# cpu_rev2.net
KiCad netlist of a schematic drawn in Altium Designer
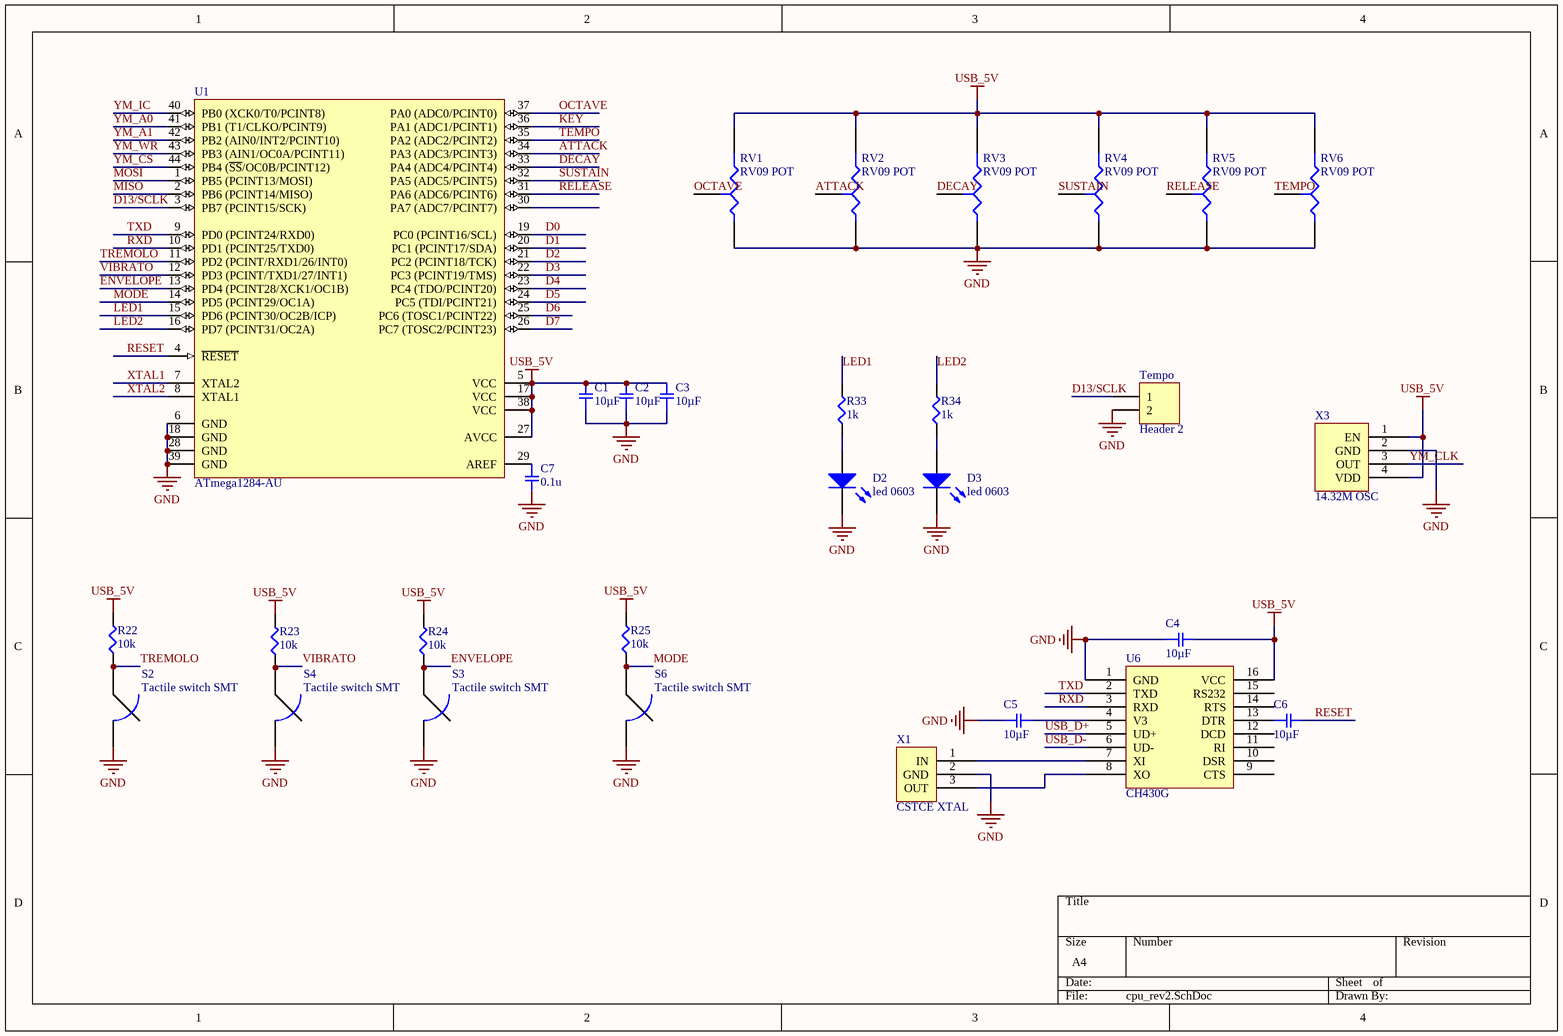
[diagram p0: cpu_rev2.SchDoc]

(export (version "E")
  (design (tool "Eeschema 10.0.6"))
  (components
    (comp (ref "C1")
      (value "10µF")
      (footprint "SMD-0805C")
      (description "CAP CER 10UF 6.3V X5R 0805")
      (fields
        (field (name "DIGI-KEY PART NUMBER") "490-3340-1-ND")
        (field (name "PART NUMBER") "GRM219R60J106KE19D")
      )
      (libsource (lib "capacitor_murata_0805") (part "GRM219R60J106KE19D"))
    )
    (comp (ref "C2")
      (value "10µF")
      (footprint "SMD-0805C")
      (description "CAP CER 10UF 6.3V X5R 0805")
      (fields
        (field (name "DIGI-KEY PART NUMBER") "490-3340-1-ND")
        (field (name "PART NUMBER") "GRM219R60J106KE19D")
      )
      (libsource (lib "capacitor_murata_0805") (part "GRM219R60J106KE19D"))
    )
    (comp (ref "C3")
      (value "10µF")
      (footprint "SMD-0805C")
      (description "CAP CER 10UF 6.3V X5R 0805")
      (fields
        (field (name "DIGI-KEY PART NUMBER") "490-3340-1-ND")
        (field (name "PART NUMBER") "GRM219R60J106KE19D")
      )
      (libsource (lib "capacitor_murata_0805") (part "GRM219R60J106KE19D"))
    )
    (comp (ref "C4")
      (value "10µF")
      (footprint "SMD-0805C")
      (description "CAP CER 10UF 6.3V X5R 0805")
      (fields
        (field (name "DIGI-KEY PART NUMBER") "490-3340-1-ND")
        (field (name "PART NUMBER") "GRM219R60J106KE19D")
      )
      (libsource (lib "capacitor_murata_0805") (part "GRM219R60J106KE19D"))
    )
    (comp (ref "C5")
      (value "10µF")
      (footprint "SMD-0805C")
      (description "CAP CER 10UF 6.3V X5R 0805")
      (fields
        (field (name "DIGI-KEY PART NUMBER") "490-3340-1-ND")
        (field (name "PART NUMBER") "GRM219R60J106KE19D")
      )
      (libsource (lib "capacitor_murata_0805") (part "GRM219R60J106KE19D"))
    )
    (comp (ref "C6")
      (value "10µF")
      (footprint "SMD-0805C")
      (description "CAP CER 10UF 6.3V X5R 0805")
      (fields
        (field (name "DIGI-KEY PART NUMBER") "490-3340-1-ND")
        (field (name "PART NUMBER") "GRM219R60J106KE19D")
      )
      (libsource (lib "capacitor_murata_0805") (part "GRM219R60J106KE19D"))
    )
    (comp (ref "C7")
      (value "0.1u")
      (footprint "SMD-0805C")
      (description "CAP CER 10000PF 25V X7R 0805")
      (fields
        (field (name "DIGI-KEY PART NUMBER") "490-12748-1-ND")
        (field (name "PART NUMBER") "GRM216R71E103KA01D")
      )
      (libsource (lib "capacitor_murata_0805") (part "GRM216R71E103KA01D"))
    )
    (comp (ref "D2")
      (value "led 0603")
      (footprint "led 0603")
      (libsource (lib "honglong_library") (part "led 0603"))
    )
    (comp (ref "D3")
      (value "led 0603")
      (footprint "led 0603")
      (libsource (lib "honglong_library") (part "led 0603"))
    )
    (comp (ref "R22")
      (value "10k")
      (footprint "SMD-0603-RES")
      (description "RES SMD 10K OHM 1% 1/10W 0603")
      (fields
        (field (name "PART NUMBER") "ERJ-3EKF1002V")
        (field (name "DIGI-KEY PART NUMBER") "P10.0KHCT-ND")
      )
      (libsource (lib "Panasonic_ERJ_0603") (part "ERJ-3EKF1002V"))
    )
    (comp (ref "R23")
      (value "10k")
      (footprint "SMD-0603-RES")
      (description "RES SMD 10K OHM 1% 1/10W 0603")
      (fields
        (field (name "PART NUMBER") "ERJ-3EKF1002V")
        (field (name "DIGI-KEY PART NUMBER") "P10.0KHCT-ND")
      )
      (libsource (lib "Panasonic_ERJ_0603") (part "ERJ-3EKF1002V"))
    )
    (comp (ref "R24")
      (value "10k")
      (footprint "SMD-0603-RES")
      (description "RES SMD 10K OHM 1% 1/10W 0603")
      (fields
        (field (name "PART NUMBER") "ERJ-3EKF1002V")
        (field (name "DIGI-KEY PART NUMBER") "P10.0KHCT-ND")
      )
      (libsource (lib "Panasonic_ERJ_0603") (part "ERJ-3EKF1002V"))
    )
    (comp (ref "R25")
      (value "10k")
      (footprint "SMD-0603-RES")
      (description "RES SMD 10K OHM 1% 1/10W 0603")
      (fields
        (field (name "PART NUMBER") "ERJ-3EKF1002V")
        (field (name "DIGI-KEY PART NUMBER") "P10.0KHCT-ND")
      )
      (libsource (lib "Panasonic_ERJ_0603") (part "ERJ-3EKF1002V"))
    )
    (comp (ref "R33")
      (value "1k")
      (footprint "SMD-0805-RES")
      (description "RES SMD 1K OHM 1% 1/2W 0805")
      (fields
        (field (name "PART NUMBER") "ERJ-P06F1001V")
        (field (name "DIGI-KEY PART NUMBER") "P16058CT-ND")
      )
      (libsource (lib "Panasonic_ERJ_0805") (part "ERJ-P06F1001V"))
    )
    (comp (ref "R34")
      (value "1k")
      (footprint "SMD-0805-RES")
      (description "RES SMD 1K OHM 1% 1/2W 0805")
      (fields
        (field (name "PART NUMBER") "ERJ-P06F1001V")
        (field (name "DIGI-KEY PART NUMBER") "P16058CT-ND")
      )
      (libsource (lib "Panasonic_ERJ_0805") (part "ERJ-P06F1001V"))
    )
    (comp (ref "RV1") (value "RV09 POT") (footprint "RV09") (libsource (lib "slide") (part "RV09 POT")))
    (comp (ref "RV2") (value "RV09 POT") (footprint "RV09") (libsource (lib "slide") (part "RV09 POT")))
    (comp (ref "RV3") (value "RV09 POT") (footprint "RV09") (libsource (lib "slide") (part "RV09 POT")))
    (comp (ref "RV4") (value "RV09 POT") (footprint "RV09") (libsource (lib "slide") (part "RV09 POT")))
    (comp (ref "RV5") (value "RV09 POT") (footprint "RV09") (libsource (lib "slide") (part "RV09 POT")))
    (comp (ref "RV6") (value "RV09 POT") (footprint "RV09") (libsource (lib "slide") (part "RV09 POT")))
    (comp (ref "S2")
      (value "Tactile switch SMT")
      (footprint "Tactile switch SMT")
      (libsource (lib "roundie") (part "Tactile switch SMT"))
    )
    (comp (ref "S3")
      (value "Tactile switch SMT")
      (footprint "Tactile switch SMT")
      (libsource (lib "roundie") (part "Tactile switch SMT"))
    )
    (comp (ref "S4")
      (value "Tactile switch SMT")
      (footprint "Tactile switch SMT")
      (libsource (lib "roundie") (part "Tactile switch SMT"))
    )
    (comp (ref "S6")
      (value "Tactile switch SMT")
      (footprint "Tactile switch SMT")
      (libsource (lib "roundie") (part "Tactile switch SMT"))
    )
    (comp (ref "Tempo")
      (value "Header 2")
      (footprint "HDR1X2")
      (description "Header, 2-Pin")
      (fields (field (name "PUBLISHER") "Altium Limited"))
      (libsource (lib "Miscellaneous Connectors") (part "Header 2"))
    )
    (comp (ref "U1")
      (value "ATmega1284-AU")
      (footprint "44A_N")
      (fields (field (name "PUBLISHER") "Altium Limited"))
      (libsource (lib "Atmel Microcontroller 8-Bit megaAVR") (part "ATmega1284-AU"))
    )
    (comp (ref "U6") (value "CH430G") (footprint "CH430G") (libsource (lib "slide") (part "CH430G")))
    (comp (ref "X1")
      (value "CSTCE XTAL")
      (footprint "CSTCE-CCM-R0")
      (description "CST XTAL")
      (libsource (lib "slide") (part "CSTCE XTAL"))
    )
    (comp (ref "X3") (value "14.32M OSC") (footprint "OSC") (libsource (lib "slide") (part "14.32M OSC")))
  )
  (nets
    (net (code "1") (name "/ATTACK") (class "Default")
      (node (ref "RV2") (pin "2") (pinfunction "TAP_2") (pintype "passive"))
      (node (ref "U1") (pin "34") (pinfunction "PA3_(ADC3/PCINT3)_34") (pintype "bidirectional"))
    )
    (net (code "2") (name "/D0") (class "Default")
      (node (ref "U1") (pin "19") (pinfunction "PC0_(PCINT16/SCL)_19") (pintype "bidirectional"))
    )
    (net (code "3") (name "/D1") (class "Default")
      (node (ref "U1") (pin "20") (pinfunction "PC1_(PCINT17/SDA)_20") (pintype "bidirectional"))
    )
    (net (code "4") (name "/D2") (class "Default")
      (node (ref "U1") (pin "21") (pinfunction "PC2_(PCINT18/TCK)_21") (pintype "bidirectional"))
    )
    (net (code "5") (name "/D3") (class "Default")
      (node (ref "U1") (pin "22") (pinfunction "PC3_(PCINT19/TMS)_22") (pintype "bidirectional"))
    )
    (net (code "6") (name "/D4") (class "Default")
      (node (ref "U1") (pin "23") (pinfunction "PC4_(TDO/PCINT20)_23") (pintype "bidirectional"))
    )
    (net (code "7") (name "/D5") (class "Default")
      (node (ref "U1") (pin "24") (pinfunction "PC5_(TDI/PCINT21)_24") (pintype "bidirectional"))
    )
    (net (code "8") (name "/D6") (class "Default")
      (node (ref "U1") (pin "25") (pinfunction "PC6_(TOSC1/PCINT22)_25") (pintype "bidirectional"))
    )
    (net (code "9") (name "/D7") (class "Default")
      (node (ref "U1") (pin "26") (pinfunction "PC7_(TOSC2/PCINT23)_26") (pintype "bidirectional"))
    )
    (net (code "10") (name "/D13{slash}SCLK") (class "Default")
      (node (ref "Tempo") (pin "1") (pinfunction "1_1") (pintype "passive"))
      (node (ref "U1") (pin "3") (pinfunction "PB7_(PCINT15/SCK)_3") (pintype "bidirectional"))
    )
    (net (code "11") (name "/DECAY") (class "Default")
      (node (ref "RV3") (pin "2") (pinfunction "TAP_2") (pintype "passive"))
      (node (ref "U1") (pin "33") (pinfunction "PA4_(ADC4/PCINT4)_33") (pintype "bidirectional"))
    )
    (net (code "12") (name "/ENVELOPE") (class "Default")
      (node (ref "R24") (pin "1") (pinfunction "1_1") (pintype "passive"))
      (node (ref "S3") (pin "1") (pinfunction "1_1") (pintype "passive"))
      (node (ref "U1") (pin "13") (pinfunction "PD4_(PCINT28/XCK1/OC1B)_13") (pintype "bidirectional"))
    )
    (net (code "13") (name "/KEY") (class "Default")
      (node (ref "U1") (pin "36") (pinfunction "PA1_(ADC1/PCINT1)_36") (pintype "bidirectional"))
    )
    (net (code "14") (name "/LED1") (class "Default")
      (node (ref "R33") (pin "2") (pinfunction "2_2") (pintype "passive"))
      (node (ref "U1") (pin "15") (pinfunction "PD6_(PCINT30/OC2B/ICP)_15") (pintype "bidirectional"))
    )
    (net (code "15") (name "/LED2") (class "Default")
      (node (ref "R34") (pin "2") (pinfunction "2_2") (pintype "passive"))
      (node (ref "U1") (pin "16") (pinfunction "PD7_(PCINT31/OC2A)_16") (pintype "bidirectional"))
    )
    (net (code "16") (name "/MISO") (class "Default")
      (node (ref "U1") (pin "2") (pinfunction "PB6_(PCINT14/MISO)_2") (pintype "bidirectional"))
    )
    (net (code "17") (name "/MODE") (class "Default")
      (node (ref "R25") (pin "1") (pinfunction "1_1") (pintype "passive"))
      (node (ref "S6") (pin "1") (pinfunction "1_1") (pintype "passive"))
      (node (ref "U1") (pin "14") (pinfunction "PD5_(PCINT29/OC1A)_14") (pintype "bidirectional"))
    )
    (net (code "18") (name "/MOSI") (class "Default")
      (node (ref "U1") (pin "1") (pinfunction "PB5_(PCINT13/MOSI)_1") (pintype "bidirectional"))
    )
    (net (code "19") (name "/OCTAVE") (class "Default")
      (node (ref "RV1") (pin "2") (pinfunction "TAP_2") (pintype "passive"))
      (node (ref "U1") (pin "37") (pinfunction "PA0_(ADC0/PCINT0)_37") (pintype "bidirectional"))
    )
    (net (code "20") (name "/RELEASE") (class "Default")
      (node (ref "RV5") (pin "2") (pinfunction "TAP_2") (pintype "passive"))
      (node (ref "U1") (pin "31") (pinfunction "PA6_(ADC6/PCINT6)_31") (pintype "bidirectional"))
    )
    (net (code "21") (name "/RESET") (class "Default")
      (node (ref "C6") (pin "2") (pinfunction "2_2") (pintype "passive"))
      (node (ref "U1") (pin "4") (pinfunction "~{RESET}_4") (pintype "input"))
    )
    (net (code "22") (name "/RXD") (class "Default")
      (node (ref "U1") (pin "10") (pinfunction "PD1_(PCINT25/TXD0)_10") (pintype "bidirectional"))
      (node (ref "U6") (pin "3") (pinfunction "RXD_3") (pintype "passive"))
    )
    (net (code "23") (name "/SUSTAIN") (class "Default")
      (node (ref "RV4") (pin "2") (pinfunction "TAP_2") (pintype "passive"))
      (node (ref "U1") (pin "32") (pinfunction "PA5_(ADC5/PCINT5)_32") (pintype "bidirectional"))
    )
    (net (code "24") (name "/TEMPO") (class "Default")
      (node (ref "RV6") (pin "2") (pinfunction "TAP_2") (pintype "passive"))
      (node (ref "U1") (pin "35") (pinfunction "PA2_(ADC2/PCINT2)_35") (pintype "bidirectional"))
    )
    (net (code "25") (name "/TREMOLO") (class "Default")
      (node (ref "R22") (pin "1") (pinfunction "1_1") (pintype "passive"))
      (node (ref "S2") (pin "1") (pinfunction "1_1") (pintype "passive"))
      (node (ref "U1") (pin "11") (pinfunction "PD2_(PCINT/RXD1/26/INT0)_11") (pintype "bidirectional"))
    )
    (net (code "26") (name "/TXD") (class "Default")
      (node (ref "U1") (pin "9") (pinfunction "PD0_(PCINT24/RXD0)_9") (pintype "bidirectional"))
      (node (ref "U6") (pin "2") (pinfunction "TXD_2") (pintype "passive"))
    )
    (net (code "27") (name "/USB_D+") (class "Default")
      (node (ref "U6") (pin "5") (pinfunction "UD+_5") (pintype "passive"))
    )
    (net (code "28") (name "/USB_D-") (class "Default")
      (node (ref "U6") (pin "6") (pinfunction "UD-_6") (pintype "passive"))
    )
    (net (code "29") (name "/VIBRATO") (class "Default")
      (node (ref "R23") (pin "1") (pinfunction "1_1") (pintype "passive"))
      (node (ref "S4") (pin "1") (pinfunction "1_1") (pintype "passive"))
      (node (ref "U1") (pin "12") (pinfunction "PD3_(PCINT/TXD1/27/INT1)_12") (pintype "bidirectional"))
    )
    (net (code "30") (name "/XTAL1") (class "Default")
      (node (ref "U1") (pin "7") (pinfunction "XTAL2_7") (pintype "passive"))
    )
    (net (code "31") (name "/XTAL2") (class "Default")
      (node (ref "U1") (pin "8") (pinfunction "XTAL1_8") (pintype "passive"))
    )
    (net (code "32") (name "/YM_A0") (class "Default")
      (node (ref "U1") (pin "41") (pinfunction "PB1_(T1/CLKO/PCINT9)_41") (pintype "bidirectional"))
    )
    (net (code "33") (name "/YM_A1") (class "Default")
      (node (ref "U1") (pin "42") (pinfunction "PB2_(AIN0/INT2/PCINT10)_42") (pintype "bidirectional"))
    )
    (net (code "34") (name "/YM_CLK") (class "Default")
      (node (ref "X3") (pin "3") (pinfunction "OUT_3") (pintype "passive"))
    )
    (net (code "35") (name "/YM_CS") (class "Default")
      (node (ref "U1") (pin "44") (pinfunction "PB4_(~{SS}/OC0B/PCINT12)_44") (pintype "bidirectional"))
    )
    (net (code "36") (name "/YM_IC") (class "Default")
      (node (ref "U1") (pin "40") (pinfunction "PB0_(XCK0/T0/PCINT8)_40") (pintype "bidirectional"))
    )
    (net (code "37") (name "/YM_WR") (class "Default")
      (node (ref "U1") (pin "43") (pinfunction "PB3_(AIN1/OC0A/PCINT11)_43") (pintype "bidirectional"))
    )
    (net (code "38") (name "GND") (class "Default")
      (node (ref "C1") (pin "1") (pinfunction "1_1") (pintype "passive"))
      (node (ref "C2") (pin "1") (pinfunction "1_1") (pintype "passive"))
      (node (ref "C3") (pin "1") (pinfunction "1_1") (pintype "passive"))
      (node (ref "C4") (pin "1") (pinfunction "1_1") (pintype "passive"))
      (node (ref "C5") (pin "1") (pinfunction "1_1") (pintype "passive"))
      (node (ref "C7") (pin "2") (pinfunction "2_2") (pintype "passive"))
      (node (ref "D2") (pin "2") (pinfunction "2_2") (pintype "passive"))
      (node (ref "D3") (pin "2") (pinfunction "2_2") (pintype "passive"))
      (node (ref "RV1") (pin "1") (pinfunction "A_1") (pintype "passive"))
      (node (ref "RV2") (pin "1") (pinfunction "A_1") (pintype "passive"))
      (node (ref "RV3") (pin "1") (pinfunction "A_1") (pintype "passive"))
      (node (ref "RV4") (pin "1") (pinfunction "A_1") (pintype "passive"))
      (node (ref "RV5") (pin "1") (pinfunction "A_1") (pintype "passive"))
      (node (ref "RV6") (pin "1") (pinfunction "A_1") (pintype "passive"))
      (node (ref "S2") (pin "2") (pinfunction "2_2") (pintype "passive"))
      (node (ref "S3") (pin "2") (pinfunction "2_2") (pintype "passive"))
      (node (ref "S4") (pin "2") (pinfunction "2_2") (pintype "passive"))
      (node (ref "S6") (pin "2") (pinfunction "2_2") (pintype "passive"))
      (node (ref "Tempo") (pin "2") (pinfunction "2_2") (pintype "passive"))
      (node (ref "U1") (pin "18") (pinfunction "GND_18") (pintype "power_in"))
      (node (ref "U1") (pin "28") (pinfunction "GND_28") (pintype "power_in"))
      (node (ref "U1") (pin "39") (pinfunction "GND_39") (pintype "power_in"))
      (node (ref "U1") (pin "6") (pinfunction "GND_6") (pintype "power_in"))
      (node (ref "U6") (pin "1") (pinfunction "GND_1") (pintype "passive"))
      (node (ref "X1") (pin "2") (pinfunction "GND_2") (pintype "passive"))
      (node (ref "X3") (pin "2") (pinfunction "GND_2") (pintype "passive"))
    )
    (net (code "39") (name "Net-(D2-Pad1)") (class "Default")
      (node (ref "D2") (pin "1") (pinfunction "1_1") (pintype "passive"))
      (node (ref "R33") (pin "1") (pinfunction "1_1") (pintype "passive"))
    )
    (net (code "40") (name "Net-(D3-Pad1)") (class "Default")
      (node (ref "D3") (pin "1") (pinfunction "1_1") (pintype "passive"))
      (node (ref "R34") (pin "1") (pinfunction "1_1") (pintype "passive"))
    )
    (net (code "41") (name "Net-(U1-AREF)") (class "Default")
      (node (ref "C7") (pin "1") (pinfunction "1_1") (pintype "passive"))
      (node (ref "U1") (pin "29") (pinfunction "AREF_29") (pintype "power_in"))
    )
    (net (code "42") (name "Net-(U6-DTR)") (class "Default")
      (node (ref "C6") (pin "1") (pinfunction "1_1") (pintype "passive"))
      (node (ref "U6") (pin "13") (pinfunction "DTR_13") (pintype "passive"))
    )
    (net (code "43") (name "Net-(U6-V3)") (class "Default")
      (node (ref "C5") (pin "2") (pinfunction "2_2") (pintype "passive"))
      (node (ref "U6") (pin "4") (pinfunction "V3_4") (pintype "passive"))
    )
    (net (code "44") (name "Net-(U6-XI)") (class "Default")
      (node (ref "U6") (pin "7") (pinfunction "XI_7") (pintype "passive"))
      (node (ref "X1") (pin "1") (pinfunction "IN_1") (pintype "passive"))
    )
    (net (code "45") (name "Net-(U6-XO)") (class "Default")
      (node (ref "U6") (pin "8") (pinfunction "XO_8") (pintype "passive"))
      (node (ref "X1") (pin "3") (pinfunction "OUT_3") (pintype "passive"))
    )
    (net (code "46") (name "USB_5V") (class "Default")
      (node (ref "C1") (pin "2") (pinfunction "2_2") (pintype "passive"))
      (node (ref "C2") (pin "2") (pinfunction "2_2") (pintype "passive"))
      (node (ref "C3") (pin "2") (pinfunction "2_2") (pintype "passive"))
      (node (ref "C4") (pin "2") (pinfunction "2_2") (pintype "passive"))
      (node (ref "R22") (pin "2") (pinfunction "2_2") (pintype "passive"))
      (node (ref "R23") (pin "2") (pinfunction "2_2") (pintype "passive"))
      (node (ref "R24") (pin "2") (pinfunction "2_2") (pintype "passive"))
      (node (ref "R25") (pin "2") (pinfunction "2_2") (pintype "passive"))
      (node (ref "RV1") (pin "3") (pinfunction "B_3") (pintype "passive"))
      (node (ref "RV2") (pin "3") (pinfunction "B_3") (pintype "passive"))
      (node (ref "RV3") (pin "3") (pinfunction "B_3") (pintype "passive"))
      (node (ref "RV4") (pin "3") (pinfunction "B_3") (pintype "passive"))
      (node (ref "RV5") (pin "3") (pinfunction "B_3") (pintype "passive"))
      (node (ref "RV6") (pin "3") (pinfunction "B_3") (pintype "passive"))
      (node (ref "U1") (pin "17") (pinfunction "VCC_17") (pintype "power_in"))
      (node (ref "U1") (pin "27") (pinfunction "AVCC_27") (pintype "power_in"))
      (node (ref "U1") (pin "38") (pinfunction "VCC_38") (pintype "power_in"))
      (node (ref "U1") (pin "5") (pinfunction "VCC_5") (pintype "power_in"))
      (node (ref "U6") (pin "16") (pinfunction "VCC_16") (pintype "passive"))
      (node (ref "X3") (pin "1") (pinfunction "EN_1") (pintype "passive"))
      (node (ref "X3") (pin "4") (pinfunction "VDD_4") (pintype "passive"))
    )
    (net (code "47") (name "unconnected-(U1-PA7_(ADC7{slash}PCINT7)-Pad30)") (class "Default")
      (node (ref "U1") (pin "30") (pinfunction "PA7_(ADC7/PCINT7)_30") (pintype "bidirectional"))
    )
    (net (code "48") (name "unconnected-(U6-CTS-Pad9)") (class "Default")
      (node (ref "U6") (pin "9") (pinfunction "CTS_9") (pintype "passive"))
    )
    (net (code "49") (name "unconnected-(U6-DCD-Pad12)") (class "Default")
      (node (ref "U6") (pin "12") (pinfunction "DCD_12") (pintype "passive"))
    )
    (net (code "50") (name "unconnected-(U6-DSR-Pad10)") (class "Default")
      (node (ref "U6") (pin "10") (pinfunction "DSR_10") (pintype "passive"))
    )
    (net (code "51") (name "unconnected-(U6-RI-Pad11)") (class "Default")
      (node (ref "U6") (pin "11") (pinfunction "RI_11") (pintype "passive"))
    )
    (net (code "52") (name "unconnected-(U6-RS232-Pad15)") (class "Default")
      (node (ref "U6") (pin "15") (pinfunction "RS232_15") (pintype "passive"))
    )
    (net (code "53") (name "unconnected-(U6-RTS-Pad14)") (class "Default")
      (node (ref "U6") (pin "14") (pinfunction "RTS_14") (pintype "passive"))
    )
  )
)
